# LightSwitch2.net
KiCad netlist of a schematic drawn in EAGLE
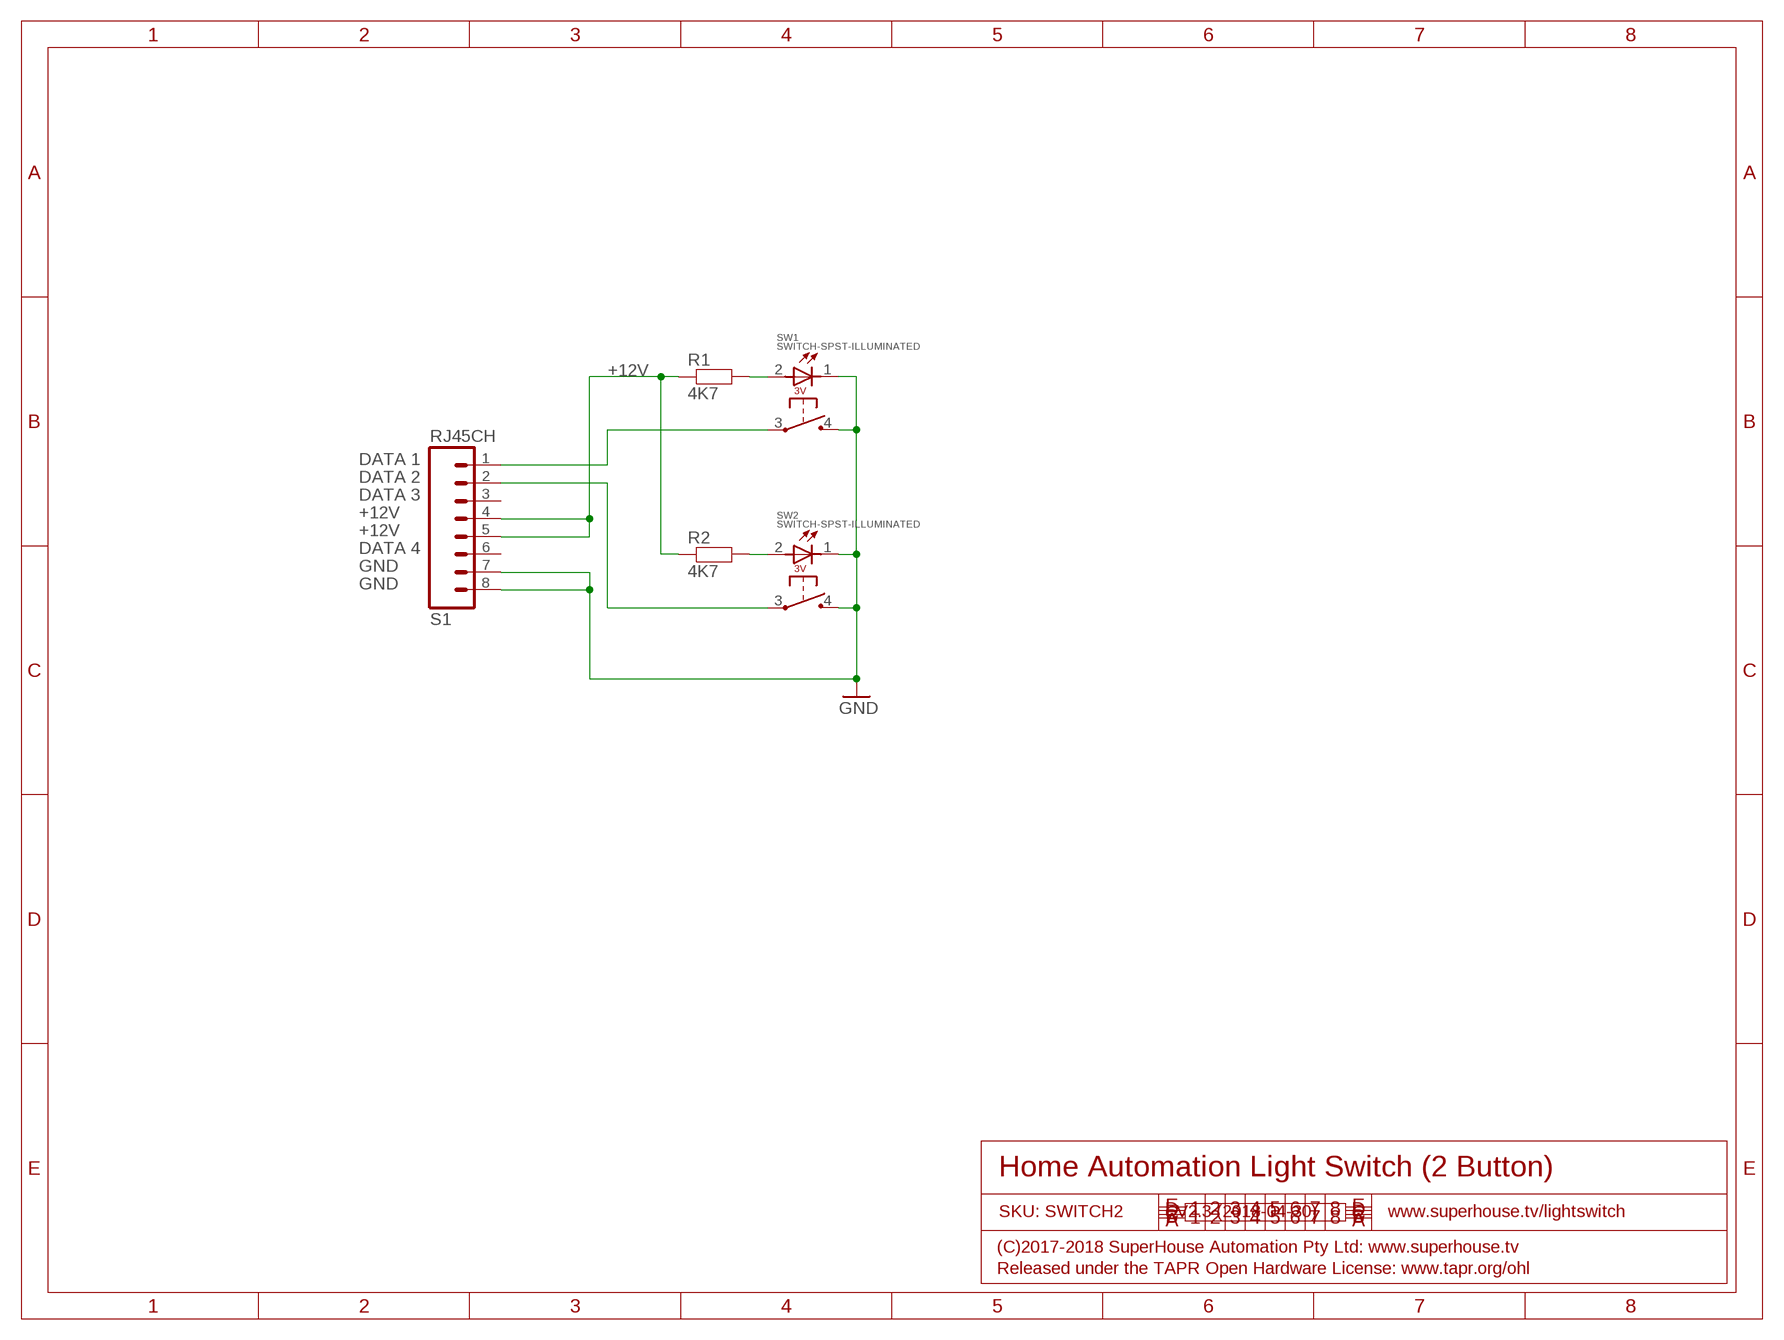
[diagram p0: schematic, sheet 1]

(export (version "E")
  (design (tool "Eeschema 10.0.6"))
  (components
    (comp (ref "R1")
      (value "4K7")
      (footprint "eagle-import:0603")
      (libsource (lib "eagle-import") (part "RESISTOR0603"))
    )
    (comp (ref "R2")
      (value "4K7")
      (footprint "eagle-import:0603")
      (libsource (lib "eagle-import") (part "RESISTOR0603"))
    )
    (comp (ref "S1")
      (value "RJ45CH")
      (footprint "eagle-import:RJ45CH")
      (libsource (lib "eagle-import") (part "RJ45CH"))
    )
    (comp (ref "SW1")
      (value "SWITCH-SPST-ILLUMINATED")
      (footprint "eagle-import:SWITCH-SPST-ILLUMINATED")
      (libsource (lib "eagle-import") (part "SWITCH-SPST-ILLUMINATED"))
    )
    (comp (ref "SW2")
      (value "SWITCH-SPST-ILLUMINATED")
      (footprint "eagle-import:SWITCH-SPST-ILLUMINATED")
      (libsource (lib "eagle-import") (part "SWITCH-SPST-ILLUMINATED"))
    )
  )
  (nets
    (net (code "1") (name "/+12V") (class "Default")
      (node (ref "R1") (pin "1") (pinfunction "1_1") (pintype "passive"))
      (node (ref "R2") (pin "1") (pinfunction "1_1") (pintype "passive"))
      (node (ref "S1") (pin "4") (pinfunction "4_4") (pintype "passive"))
      (node (ref "S1") (pin "5") (pinfunction "5_5") (pintype "passive"))
    )
    (net (code "2") (name "GND") (class "Default")
      (node (ref "S1") (pin "7") (pinfunction "7_7") (pintype "passive"))
      (node (ref "S1") (pin "8") (pinfunction "8_8") (pintype "passive"))
      (node (ref "SW1") (pin "1") (pinfunction "-_1") (pintype "passive"))
      (node (ref "SW1") (pin "4") (pinfunction "NO_4") (pintype "passive"))
      (node (ref "SW2") (pin "1") (pinfunction "-_1") (pintype "passive"))
      (node (ref "SW2") (pin "4") (pinfunction "NO_4") (pintype "passive"))
    )
    (net (code "3") (name "Net-(SW1-+)") (class "Default")
      (node (ref "R1") (pin "2") (pinfunction "2_2") (pintype "passive"))
      (node (ref "SW1") (pin "2") (pinfunction "+_2") (pintype "passive"))
    )
    (net (code "4") (name "Net-(SW1-COM)") (class "Default")
      (node (ref "S1") (pin "1") (pinfunction "1_1") (pintype "passive"))
      (node (ref "SW1") (pin "3") (pinfunction "COM_3") (pintype "passive"))
    )
    (net (code "5") (name "Net-(SW2-+)") (class "Default")
      (node (ref "R2") (pin "2") (pinfunction "2_2") (pintype "passive"))
      (node (ref "SW2") (pin "2") (pinfunction "+_2") (pintype "passive"))
    )
    (net (code "6") (name "Net-(SW2-COM)") (class "Default")
      (node (ref "S1") (pin "2") (pinfunction "2_2") (pintype "passive"))
      (node (ref "SW2") (pin "3") (pinfunction "COM_3") (pintype "passive"))
    )
    (net (code "7") (name "unconnected-(S1-Pad3)") (class "Default")
      (node (ref "S1") (pin "3") (pinfunction "3_3") (pintype "passive"))
    )
    (net (code "8") (name "unconnected-(S1-Pad6)") (class "Default")
      (node (ref "S1") (pin "6") (pinfunction "6_6") (pintype "passive"))
    )
  )
)
